# untitled.net
KiCad netlist of a schematic drawn in EAGLE
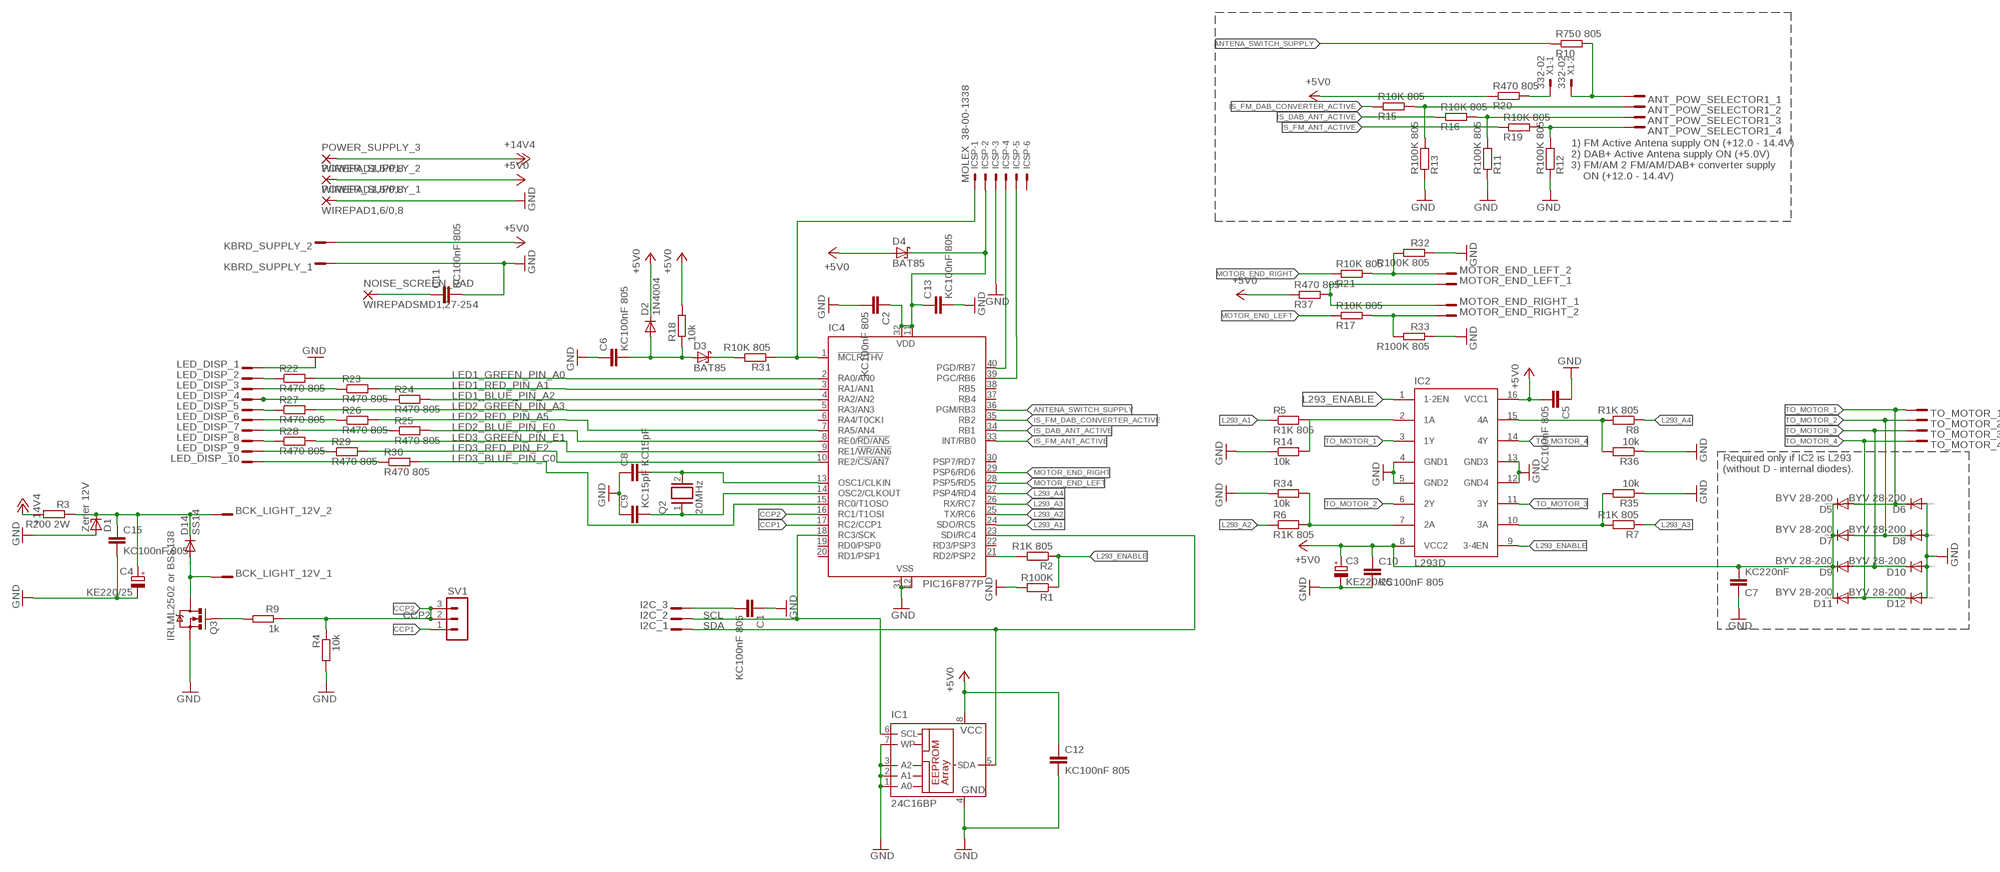
[diagram p0: schematic, sheet 1]

(export (version "E")
  (design (tool "Eeschema 10.0.6"))
  (components
    (comp (ref "ANT_POW_SELECTOR1")
      (value "JST_4_PIN_B4B-PH-KS")
      (footprint "eagle-import:B4B-PH-KS")
      (libsource (lib "eagle-import") (part "JST_4_PIN_B4B-PH-KS"))
    )
    (comp (ref "BCK_LIGHT_12V")
      (value "JST_2_PIN_B2B-XH-A")
      (footprint "eagle-import:B2B-XH-A")
      (libsource (lib "eagle-import") (part "JST_2_PIN_B2B-XH-A"))
    )
    (comp (ref "C1")
      (value "KC100nF 805")
      (footprint "eagle-import:C0805")
      (libsource (lib "eagle-import") (part "C-EUC0805"))
    )
    (comp (ref "C2")
      (value "KC100nF 805")
      (footprint "eagle-import:C0805")
      (libsource (lib "eagle-import") (part "C-EUC0805"))
    )
    (comp (ref "C3")
      (value "KE220/25")
      (footprint "eagle-import:E3,5-8")
      (libsource (lib "eagle-import") (part "CPOL-EUE3.5-8"))
    )
    (comp (ref "C4")
      (value "KE220/25")
      (footprint "eagle-import:TT2D7")
      (libsource (lib "eagle-import") (part "CPOL-EUTT2D7"))
    )
    (comp (ref "C5")
      (value "KC100nF 805")
      (footprint "eagle-import:C0805")
      (libsource (lib "eagle-import") (part "C-EUC0805"))
    )
    (comp (ref "C6")
      (value "KC100nF 805")
      (footprint "eagle-import:C0805")
      (libsource (lib "eagle-import") (part "C-EUC0805"))
    )
    (comp (ref "C7")
      (value "KC220nF")
      (footprint "eagle-import:C050-030X075")
      (libsource (lib "eagle-import") (part "C-EU050-030X075"))
    )
    (comp (ref "C8")
      (value "KC15pF")
      (footprint "eagle-import:C025-030X050")
      (libsource (lib "eagle-import") (part "C-EU025-030X050"))
    )
    (comp (ref "C9")
      (value "KC15pF")
      (footprint "eagle-import:C025-030X050")
      (libsource (lib "eagle-import") (part "C-EU025-030X050"))
    )
    (comp (ref "C10")
      (value "KC100nF 805")
      (footprint "eagle-import:C0805")
      (libsource (lib "eagle-import") (part "C-EUC0805"))
    )
    (comp (ref "C11")
      (value "KC100nF 805")
      (footprint "eagle-import:C0805")
      (libsource (lib "eagle-import") (part "C-EUC0805"))
    )
    (comp (ref "C12")
      (value "KC100nF 805")
      (footprint "eagle-import:C0805")
      (libsource (lib "eagle-import") (part "C-EUC0805"))
    )
    (comp (ref "C13")
      (value "KC100nF 805")
      (footprint "eagle-import:C0805")
      (libsource (lib "eagle-import") (part "C-EUC0805"))
    )
    (comp (ref "C15")
      (value "KC100nF 805")
      (footprint "eagle-import:C0805")
      (libsource (lib "eagle-import") (part "C-EUC0805"))
    )
    (comp (ref "D1")
      (value "Zener 12V")
      (footprint "eagle-import:ZDIO-5")
      (libsource (lib "eagle-import") (part "ZENER-DIODEZD-5"))
    )
    (comp (ref "D2")
      (value "1N4004")
      (footprint "eagle-import:DO41-7.6")
      (libsource (lib "eagle-import") (part "1N4004DO41-7.6"))
    )
    (comp (ref "D3")
      (value "BAT85")
      (footprint "eagle-import:DO34-5")
      (libsource (lib "eagle-import") (part "BAT85DO34-5"))
    )
    (comp (ref "D4")
      (value "BAT85")
      (footprint "eagle-import:DO34-5")
      (libsource (lib "eagle-import") (part "BAT85DO34-5"))
    )
    (comp (ref "D5")
      (value "BYV 28-200")
      (footprint "eagle-import:SOD64-10")
      (libsource (lib "eagle-import") (part "BYV28"))
    )
    (comp (ref "D6")
      (value "BYV 28-200")
      (footprint "eagle-import:SOD64-10")
      (libsource (lib "eagle-import") (part "BYV28"))
    )
    (comp (ref "D7")
      (value "BYV 28-200")
      (footprint "eagle-import:SOD64-10")
      (libsource (lib "eagle-import") (part "BYV28"))
    )
    (comp (ref "D8")
      (value "BYV 28-200")
      (footprint "eagle-import:SOD64-10")
      (libsource (lib "eagle-import") (part "BYV28"))
    )
    (comp (ref "D9")
      (value "BYV 28-200")
      (footprint "eagle-import:SOD64-10")
      (libsource (lib "eagle-import") (part "BYV28"))
    )
    (comp (ref "D10")
      (value "BYV 28-200")
      (footprint "eagle-import:SOD64-10")
      (libsource (lib "eagle-import") (part "BYV28"))
    )
    (comp (ref "D11")
      (value "BYV 28-200")
      (footprint "eagle-import:SOD64-10")
      (libsource (lib "eagle-import") (part "BYV28"))
    )
    (comp (ref "D12")
      (value "BYV 28-200")
      (footprint "eagle-import:SOD64-10")
      (libsource (lib "eagle-import") (part "BYV28"))
    )
    (comp (ref "D14")
      (value "SS14")
      (footprint "eagle-import:SMB")
      (libsource (lib "eagle-import") (part "DIODE-SMB"))
    )
    (comp (ref "I2C")
      (value "JST_3_PIN_B3B-PH-KS")
      (footprint "eagle-import:B3B-PH-KS")
      (libsource (lib "eagle-import") (part "JST_3_PIN_B3B-PH-KS"))
    )
    (comp (ref "IC1")
      (value "24C16BP")
      (footprint "eagle-import:DIL8")
      (fields (field (name "MPN") "AT24C16B-PU"))
      (libsource (lib "eagle-import") (part "24PC16B"))
    )
    (comp (ref "IC2")
      (value "L293D")
      (footprint "eagle-import:DIL16")
      (libsource (lib "eagle-import") (part "L293D"))
    )
    (comp (ref "IC4")
      (value "PIC16F877P")
      (footprint "eagle-import:DIL40")
      (fields (field (name "MF") "MICROCHIP") (field (name "MPN") "PIC16F877-04/P"))
      (libsource (lib "eagle-import") (part "PIC16F87P7"))
    )
    (comp (ref "ICSP")
      (value "MOLEX 38-00-1338")
      (footprint "eagle-import:6410-06")
      (libsource (lib "eagle-import") (part "22-?-0627-2061"))
    )
    (comp (ref "KBRD_SUPPLY")
      (value "JST_2_PIN_B2B-PH-KS")
      (footprint "eagle-import:B2B-PH-KS")
      (libsource (lib "eagle-import") (part "JST_2_PIN_B2B-PH-KS"))
    )
    (comp (ref "LED_DISP")
      (value "JST_10_PIN_B10B-PH-KS")
      (footprint "eagle-import:B10B-PH-KS")
      (libsource (lib "eagle-import") (part "JST_10_PIN_B10B-PH-KS"))
    )
    (comp (ref "MOTOR_END_LEFT")
      (value "JST_2_PIN_B2B-PH-KS")
      (footprint "eagle-import:B2B-PH-KS")
      (libsource (lib "eagle-import") (part "JST_2_PIN_B2B-PH-KS"))
    )
    (comp (ref "MOTOR_END_RIGHT")
      (value "JST_2_PIN_B2B-PH-KS")
      (footprint "eagle-import:B2B-PH-KS")
      (libsource (lib "eagle-import") (part "JST_2_PIN_B2B-PH-KS"))
    )
    (comp (ref "NOISE_SCREEN_PAD")
      (value "WIREPADSMD1,27-254")
      (footprint "eagle-import:SMD1,27-2,54")
      (libsource (lib "eagle-import") (part "WIREPADSMD1,27-254"))
    )
    (comp (ref "POWER_SUPPLY_1")
      (value "WIREPAD1,6/0,8")
      (footprint "eagle-import:1,6_0,8")
      (libsource (lib "eagle-import") (part "WIREPAD1,6/0,8"))
    )
    (comp (ref "POWER_SUPPLY_2")
      (value "WIREPAD1,6/0,8")
      (footprint "eagle-import:1,6_0,8")
      (libsource (lib "eagle-import") (part "WIREPAD1,6/0,8"))
    )
    (comp (ref "POWER_SUPPLY_3")
      (value "WIREPAD1,6/0,8")
      (footprint "eagle-import:1,6_0,8")
      (libsource (lib "eagle-import") (part "WIREPAD1,6/0,8"))
    )
    (comp (ref "Q2")
      (value "20MHz")
      (footprint "eagle-import:QS")
      (libsource (lib "eagle-import") (part "XTAL/S"))
    )
    (comp (ref "Q3")
      (value "IRLML2502 or BSS138")
      (footprint "eagle-import:SOT23-3")
      (libsource (lib "eagle-import") (part "MOSFET-NCHANNELSMD"))
    )
    (comp (ref "R1")
      (value "R100K")
      (footprint "eagle-import:0204_7")
      (libsource (lib "eagle-import") (part "resistor_R-EU_0204/7"))
    )
    (comp (ref "R2")
      (value "R1K 805")
      (footprint "eagle-import:R0805")
      (libsource (lib "eagle-import") (part "resistor_R-EU_R0805"))
    )
    (comp (ref "R3")
      (value "R200 2W")
      (footprint "eagle-import:0207_12")
      (libsource (lib "eagle-import") (part "R-EU_0207/12"))
    )
    (comp (ref "R4")
      (value "10k")
      (footprint "eagle-import:M0805")
      (libsource (lib "eagle-import") (part "R-EU_M0805"))
    )
    (comp (ref "R5")
      (value "R1K 805")
      (footprint "eagle-import:R0805")
      (libsource (lib "eagle-import") (part "resistor_R-EU_R0805"))
    )
    (comp (ref "R6")
      (value "R1K 805")
      (footprint "eagle-import:R0805")
      (libsource (lib "eagle-import") (part "resistor_R-EU_R0805"))
    )
    (comp (ref "R7")
      (value "R1K 805")
      (footprint "eagle-import:R0805")
      (libsource (lib "eagle-import") (part "resistor_R-EU_R0805"))
    )
    (comp (ref "R8")
      (value "R1K 805")
      (footprint "eagle-import:R0805")
      (libsource (lib "eagle-import") (part "resistor_R-EU_R0805"))
    )
    (comp (ref "R9")
      (value "1k")
      (footprint "eagle-import:0207_12")
      (libsource (lib "eagle-import") (part "R-EU_0207/12"))
    )
    (comp (ref "R10")
      (value "R750 805")
      (footprint "eagle-import:R0805")
      (libsource (lib "eagle-import") (part "resistor_R-EU_R0805"))
    )
    (comp (ref "R11")
      (value "R100K 805")
      (footprint "eagle-import:R0805")
      (libsource (lib "eagle-import") (part "resistor_R-EU_R0805"))
    )
    (comp (ref "R12")
      (value "R100K 805")
      (footprint "eagle-import:R0805")
      (libsource (lib "eagle-import") (part "resistor_R-EU_R0805"))
    )
    (comp (ref "R13")
      (value "R100K 805")
      (footprint "eagle-import:R0805")
      (libsource (lib "eagle-import") (part "resistor_R-EU_R0805"))
    )
    (comp (ref "R14")
      (value "10k")
      (footprint "eagle-import:0204V")
      (libsource (lib "eagle-import") (part "resistor_R-EU_0204/2V"))
    )
    (comp (ref "R15")
      (value "R10K 805")
      (footprint "eagle-import:R0805")
      (libsource (lib "eagle-import") (part "resistor_R-EU_R0805"))
    )
    (comp (ref "R16")
      (value "R10K 805")
      (footprint "eagle-import:R0805")
      (libsource (lib "eagle-import") (part "resistor_R-EU_R0805"))
    )
    (comp (ref "R17")
      (value "R10K 805")
      (footprint "eagle-import:R0805")
      (libsource (lib "eagle-import") (part "resistor_R-EU_R0805"))
    )
    (comp (ref "R18")
      (value "10k")
      (footprint "eagle-import:R0805")
      (libsource (lib "eagle-import") (part "resistor_R-EU_R0805"))
    )
    (comp (ref "R19")
      (value "R10K 805")
      (footprint "eagle-import:R0805")
      (libsource (lib "eagle-import") (part "resistor_R-EU_R0805"))
    )
    (comp (ref "R20")
      (value "R470 805")
      (footprint "eagle-import:R0805")
      (libsource (lib "eagle-import") (part "resistor_R-EU_R0805"))
    )
    (comp (ref "R21")
      (value "R10K 805")
      (footprint "eagle-import:R0805")
      (libsource (lib "eagle-import") (part "resistor_R-EU_R0805"))
    )
    (comp (ref "R22")
      (value "R470 805")
      (footprint "eagle-import:R0805")
      (libsource (lib "eagle-import") (part "resistor_R-EU_R0805"))
    )
    (comp (ref "R23")
      (value "R470 805")
      (footprint "eagle-import:R0805")
      (libsource (lib "eagle-import") (part "resistor_R-EU_R0805"))
    )
    (comp (ref "R24")
      (value "R470 805")
      (footprint "eagle-import:R0805")
      (libsource (lib "eagle-import") (part "resistor_R-EU_R0805"))
    )
    (comp (ref "R25")
      (value "R470 805")
      (footprint "eagle-import:R0805")
      (libsource (lib "eagle-import") (part "resistor_R-EU_R0805"))
    )
    (comp (ref "R26")
      (value "R470 805")
      (footprint "eagle-import:R0805")
      (libsource (lib "eagle-import") (part "resistor_R-EU_R0805"))
    )
    (comp (ref "R27")
      (value "R470 805")
      (footprint "eagle-import:R0805")
      (libsource (lib "eagle-import") (part "resistor_R-EU_R0805"))
    )
    (comp (ref "R28")
      (value "R470 805")
      (footprint "eagle-import:R0805")
      (libsource (lib "eagle-import") (part "resistor_R-EU_R0805"))
    )
    (comp (ref "R29")
      (value "R470 805")
      (footprint "eagle-import:R0805")
      (libsource (lib "eagle-import") (part "resistor_R-EU_R0805"))
    )
    (comp (ref "R30")
      (value "R470 805")
      (footprint "eagle-import:R0805")
      (libsource (lib "eagle-import") (part "resistor_R-EU_R0805"))
    )
    (comp (ref "R31")
      (value "R10K 805")
      (footprint "eagle-import:R0805")
      (libsource (lib "eagle-import") (part "resistor_R-EU_R0805"))
    )
    (comp (ref "R32")
      (value "R100K 805")
      (footprint "eagle-import:R0805")
      (libsource (lib "eagle-import") (part "resistor_R-EU_R0805"))
    )
    (comp (ref "R33")
      (value "R100K 805")
      (footprint "eagle-import:R0805")
      (libsource (lib "eagle-import") (part "resistor_R-EU_R0805"))
    )
    (comp (ref "R34")
      (value "10k")
      (footprint "eagle-import:0204_5")
      (libsource (lib "eagle-import") (part "resistor_R-EU_0204/5"))
    )
    (comp (ref "R35")
      (value "10k")
      (footprint "eagle-import:0204_7")
      (libsource (lib "eagle-import") (part "resistor_R-EU_0204/7"))
    )
    (comp (ref "R36")
      (value "10k")
      (footprint "eagle-import:0204_7")
      (libsource (lib "eagle-import") (part "resistor_R-EU_0204/7"))
    )
    (comp (ref "R37")
      (value "R470 805")
      (footprint "eagle-import:R0805")
      (libsource (lib "eagle-import") (part "resistor_R-EU_R0805"))
    )
    (comp (ref "SV1")
      (value "MA03-1")
      (footprint "eagle-import:MA03-1")
      (libsource (lib "eagle-import") (part "MA03-1"))
    )
    (comp (ref "TO_MOTOR")
      (value "JST_4_PIN_B4B-XH-A")
      (footprint "eagle-import:B4B-XH-A")
      (libsource (lib "eagle-import") (part "JST_4_PIN_B4B-XH-A"))
    )
    (comp (ref "X1")
      (value "332-02")
      (footprint "eagle-import:332-02")
      (libsource (lib "eagle-import") (part "332-02"))
    )
  )
  (nets
    (net (code "1") (name "+5V0") (class "Default")
      (node (ref "C10") (pin "1") (pinfunction "1_1") (pintype "passive"))
      (node (ref "C12") (pin "1") (pinfunction "1_1") (pintype "passive"))
      (node (ref "C3") (pin "+") (pinfunction "+_+") (pintype "passive"))
      (node (ref "C5") (pin "2") (pinfunction "2_2") (pintype "passive"))
      (node (ref "C7") (pin "2") (pinfunction "2_2") (pintype "passive"))
      (node (ref "D11") (pin "C") (pinfunction "C_C") (pintype "passive"))
      (node (ref "D2") (pin "C") (pinfunction "C_C") (pintype "passive"))
      (node (ref "D4") (pin "A") (pinfunction "A_A") (pintype "passive"))
      (node (ref "D5") (pin "C") (pinfunction "C_C") (pintype "passive"))
      (node (ref "D7") (pin "C") (pinfunction "C_C") (pintype "passive"))
      (node (ref "D9") (pin "C") (pinfunction "C_C") (pintype "passive"))
      (node (ref "IC1") (pin "8") (pinfunction "VCC_8") (pintype "power_in"))
      (node (ref "IC2") (pin "16") (pinfunction "VCC1_16") (pintype "power_in"))
      (node (ref "IC2") (pin "8") (pinfunction "VCC2_8") (pintype "power_in"))
      (node (ref "KBRD_SUPPLY") (pin "P$2") (pinfunction "P$1_P$2") (pintype "bidirectional"))
      (node (ref "POWER_SUPPLY_2") (pin "1") (pinfunction "P_1") (pintype "passive"))
      (node (ref "R18") (pin "2") (pinfunction "2_2") (pintype "passive"))
      (node (ref "R20") (pin "1") (pinfunction "1_1") (pintype "passive"))
      (node (ref "R37") (pin "1") (pinfunction "1_1") (pintype "passive"))
    )
    (net (code "2") (name "+14V4") (class "Default")
      (node (ref "POWER_SUPPLY_3") (pin "1") (pinfunction "P_1") (pintype "passive"))
      (node (ref "R3") (pin "2") (pinfunction "2_2") (pintype "passive"))
    )
    (net (code "3") (name "/LED1_BLUE_PIN_A2") (class "Default")
      (node (ref "IC4") (pin "4") (pinfunction "RA2/AN2_4") (pintype "bidirectional"))
      (node (ref "R24") (pin "2") (pinfunction "2_2") (pintype "passive"))
    )
    (net (code "4") (name "/LED1_GREEN_PIN_A0") (class "Default")
      (node (ref "IC4") (pin "2") (pinfunction "RA0/AN0_2") (pintype "bidirectional"))
      (node (ref "R22") (pin "2") (pinfunction "2_2") (pintype "passive"))
    )
    (net (code "5") (name "/LED1_RED_PIN_A1") (class "Default")
      (node (ref "IC4") (pin "3") (pinfunction "RA1/AN1_3") (pintype "bidirectional"))
      (node (ref "R23") (pin "2") (pinfunction "2_2") (pintype "passive"))
    )
    (net (code "6") (name "/LED2_BLUE_PIN_E0") (class "Default")
      (node (ref "IC4") (pin "8") (pinfunction "RE0/~{RD/AN5}_8") (pintype "bidirectional"))
      (node (ref "R25") (pin "2") (pinfunction "2_2") (pintype "passive"))
    )
    (net (code "7") (name "/LED2_GREEN_PIN_A3") (class "Default")
      (node (ref "IC4") (pin "5") (pinfunction "RA3/AN3_5") (pintype "bidirectional"))
      (node (ref "R27") (pin "2") (pinfunction "2_2") (pintype "passive"))
    )
    (net (code "8") (name "/LED2_RED_PIN_A5") (class "Default")
      (node (ref "IC4") (pin "7") (pinfunction "RA5/AN4_7") (pintype "bidirectional"))
      (node (ref "R26") (pin "2") (pinfunction "2_2") (pintype "passive"))
    )
    (net (code "9") (name "/LED3_BLUE_PIN_C0") (class "Default")
      (node (ref "IC4") (pin "15") (pinfunction "RC0/T1OSO_15") (pintype "bidirectional"))
      (node (ref "R30") (pin "2") (pinfunction "2_2") (pintype "passive"))
    )
    (net (code "10") (name "/LED3_GREEN_PIN_E1") (class "Default")
      (node (ref "IC4") (pin "9") (pinfunction "RE1/~{WR/AN6}_9") (pintype "bidirectional"))
      (node (ref "R28") (pin "2") (pinfunction "2_2") (pintype "passive"))
    )
    (net (code "11") (name "/LED3_RED_PIN_E2") (class "Default")
      (node (ref "IC4") (pin "10") (pinfunction "RE2/~{CS/AN7}_10") (pintype "bidirectional"))
      (node (ref "R29") (pin "2") (pinfunction "2_2") (pintype "passive"))
    )
    (net (code "12") (name "/SCL") (class "Default")
      (node (ref "I2C") (pin "P$2") (pinfunction "P$1_P$2") (pintype "bidirectional"))
      (node (ref "IC1") (pin "6") (pinfunction "SCL_6") (pintype "input"))
      (node (ref "IC4") (pin "18") (pinfunction "RC3/SCK_18") (pintype "bidirectional"))
    )
    (net (code "13") (name "/SDA") (class "Default")
      (node (ref "I2C") (pin "P$1") (pinfunction "P$1_P$1") (pintype "bidirectional"))
      (node (ref "IC1") (pin "5") (pinfunction "SDA_5") (pintype "bidirectional"))
      (node (ref "IC4") (pin "23") (pinfunction "SDI/RC4_23") (pintype "bidirectional"))
    )
    (net (code "14") (name "ANTENA_SWITCH_SUPPLY") (class "Default")
      (node (ref "IC4") (pin "36") (pinfunction "PGM/RB3_36") (pintype "bidirectional"))
      (node (ref "R10") (pin "1") (pinfunction "1_1") (pintype "passive"))
    )
    (net (code "15") (name "CCP1") (class "Default")
      (node (ref "IC4") (pin "17") (pinfunction "RC2/CCP1_17") (pintype "bidirectional"))
      (node (ref "SV1") (pin "1") (pinfunction "1_1") (pintype "passive"))
    )
    (net (code "16") (name "CCP2") (class "Default")
      (node (ref "IC4") (pin "16") (pinfunction "RC1/T1OSI_16") (pintype "bidirectional"))
      (node (ref "R4") (pin "1") (pinfunction "1_1") (pintype "passive"))
      (node (ref "R9") (pin "1") (pinfunction "1_1") (pintype "passive"))
      (node (ref "SV1") (pin "2") (pinfunction "2_2") (pintype "passive"))
      (node (ref "SV1") (pin "3") (pinfunction "3_3") (pintype "passive"))
    )
    (net (code "17") (name "GND") (class "Default")
      (node (ref "C1") (pin "1") (pinfunction "1_1") (pintype "passive"))
      (node (ref "C10") (pin "2") (pinfunction "2_2") (pintype "passive"))
      (node (ref "C11") (pin "2") (pinfunction "2_2") (pintype "passive"))
      (node (ref "C12") (pin "2") (pinfunction "2_2") (pintype "passive"))
      (node (ref "C13") (pin "2") (pinfunction "2_2") (pintype "passive"))
      (node (ref "C15") (pin "2") (pinfunction "2_2") (pintype "passive"))
      (node (ref "C2") (pin "2") (pinfunction "2_2") (pintype "passive"))
      (node (ref "C3") (pin "-") (pinfunction "-_-") (pintype "passive"))
      (node (ref "C4") (pin "-") (pinfunction "-_-") (pintype "passive"))
      (node (ref "C5") (pin "1") (pinfunction "1_1") (pintype "passive"))
      (node (ref "C6") (pin "1") (pinfunction "1_1") (pintype "passive"))
      (node (ref "C7") (pin "1") (pinfunction "1_1") (pintype "passive"))
      (node (ref "C8") (pin "1") (pinfunction "1_1") (pintype "passive"))
      (node (ref "C9") (pin "1") (pinfunction "1_1") (pintype "passive"))
      (node (ref "D1") (pin "A") (pinfunction "A_A") (pintype "passive"))
      (node (ref "D10") (pin "A") (pinfunction "A_A") (pintype "passive"))
      (node (ref "D12") (pin "A") (pinfunction "A_A") (pintype "passive"))
      (node (ref "D6") (pin "A") (pinfunction "A_A") (pintype "passive"))
      (node (ref "D8") (pin "A") (pinfunction "A_A") (pintype "passive"))
      (node (ref "IC1") (pin "1") (pinfunction "A0_1") (pintype "input"))
      (node (ref "IC1") (pin "2") (pinfunction "A1_2") (pintype "input"))
      (node (ref "IC1") (pin "3") (pinfunction "A2_3") (pintype "input"))
      (node (ref "IC1") (pin "4") (pinfunction "GND_4") (pintype "power_in"))
      (node (ref "IC1") (pin "7") (pinfunction "WP_7") (pintype "input"))
      (node (ref "IC2") (pin "12") (pinfunction "GND4_12") (pintype "power_in"))
      (node (ref "IC2") (pin "13") (pinfunction "GND3_13") (pintype "power_in"))
      (node (ref "IC2") (pin "4") (pinfunction "GND1_4") (pintype "power_in"))
      (node (ref "IC2") (pin "5") (pinfunction "GND2_5") (pintype "power_in"))
      (node (ref "IC4") (pin "12") (pinfunction "VSS_12") (pintype "power_in"))
      (node (ref "IC4") (pin "31") (pinfunction "VSS_31") (pintype "power_in"))
      (node (ref "ICSP") (pin "3") (pinfunction "S_3") (pintype "passive"))
      (node (ref "KBRD_SUPPLY") (pin "P$1") (pinfunction "P$1_P$1") (pintype "bidirectional"))
      (node (ref "LED_DISP") (pin "P$1") (pinfunction "P$1_P$1") (pintype "bidirectional"))
      (node (ref "POWER_SUPPLY_1") (pin "1") (pinfunction "P_1") (pintype "passive"))
      (node (ref "Q3") (pin "2") (pinfunction "S_2") (pintype "passive"))
      (node (ref "R1") (pin "2") (pinfunction "2_2") (pintype "passive"))
      (node (ref "R11") (pin "1") (pinfunction "1_1") (pintype "passive"))
      (node (ref "R12") (pin "1") (pinfunction "1_1") (pintype "passive"))
      (node (ref "R13") (pin "1") (pinfunction "1_1") (pintype "passive"))
      (node (ref "R14") (pin "1") (pinfunction "1_1") (pintype "passive"))
      (node (ref "R32") (pin "1") (pinfunction "1_1") (pintype "passive"))
      (node (ref "R33") (pin "1") (pinfunction "1_1") (pintype "passive"))
      (node (ref "R34") (pin "1") (pinfunction "1_1") (pintype "passive"))
      (node (ref "R35") (pin "1") (pinfunction "1_1") (pintype "passive"))
      (node (ref "R36") (pin "1") (pinfunction "1_1") (pintype "passive"))
      (node (ref "R4") (pin "2") (pinfunction "2_2") (pintype "passive"))
    )
    (net (code "18") (name "IS_DAB_ANT_ACTIVE") (class "Default")
      (node (ref "IC4") (pin "34") (pinfunction "RB1_34") (pintype "bidirectional"))
      (node (ref "R16") (pin "1") (pinfunction "1_1") (pintype "passive"))
    )
    (net (code "19") (name "IS_FM_ANT_ACTIVE") (class "Default")
      (node (ref "IC4") (pin "33") (pinfunction "INT/RB0_33") (pintype "bidirectional"))
      (node (ref "R19") (pin "1") (pinfunction "1_1") (pintype "passive"))
    )
    (net (code "20") (name "IS_FM_DAB_CONVERTER_ACTIVE") (class "Default")
      (node (ref "IC4") (pin "35") (pinfunction "RB2_35") (pintype "bidirectional"))
      (node (ref "R15") (pin "1") (pinfunction "1_1") (pintype "passive"))
    )
    (net (code "21") (name "L293_A1") (class "Default")
      (node (ref "IC4") (pin "24") (pinfunction "SDO/RC5_24") (pintype "bidirectional"))
      (node (ref "R5") (pin "1") (pinfunction "1_1") (pintype "passive"))
    )
    (net (code "22") (name "L293_A2") (class "Default")
      (node (ref "IC4") (pin "25") (pinfunction "TX/RC6_25") (pintype "bidirectional"))
      (node (ref "R6") (pin "1") (pinfunction "1_1") (pintype "passive"))
    )
    (net (code "23") (name "L293_A3") (class "Default")
      (node (ref "IC4") (pin "26") (pinfunction "RX/RC7_26") (pintype "bidirectional"))
      (node (ref "R7") (pin "1") (pinfunction "1_1") (pintype "passive"))
    )
    (net (code "24") (name "L293_A4") (class "Default")
      (node (ref "IC4") (pin "27") (pinfunction "PSP4/RD4_27") (pintype "bidirectional"))
      (node (ref "R8") (pin "1") (pinfunction "1_1") (pintype "passive"))
    )
    (net (code "25") (name "L293_ENABLE") (class "Default")
      (node (ref "IC2") (pin "1") (pinfunction "1-2EN_1") (pintype "input"))
      (node (ref "IC2") (pin "9") (pinfunction "3-4EN_9") (pintype "input"))
      (node (ref "R1") (pin "1") (pinfunction "1_1") (pintype "passive"))
      (node (ref "R2") (pin "1") (pinfunction "1_1") (pintype "passive"))
    )
    (net (code "26") (name "MOTOR_END_LEFT") (class "Default")
      (node (ref "IC4") (pin "28") (pinfunction "PSP5/RD5_28") (pintype "bidirectional"))
      (node (ref "R17") (pin "1") (pinfunction "1_1") (pintype "passive"))
    )
    (net (code "27") (name "MOTOR_END_RIGHT") (class "Default")
      (node (ref "IC4") (pin "29") (pinfunction "PSP6/RD6_29") (pintype "bidirectional"))
      (node (ref "R21") (pin "1") (pinfunction "1_1") (pintype "passive"))
    )
    (net (code "28") (name "Net-(ANT_POW_SELECTOR1B-P$1)") (class "Default")
      (node (ref "ANT_POW_SELECTOR1") (pin "P$2") (pinfunction "P$1_P$2") (pintype "bidirectional"))
      (node (ref "R13") (pin "2") (pinfunction "2_2") (pintype "passive"))
      (node (ref "R15") (pin "2") (pinfunction "2_2") (pintype "passive"))
    )
    (net (code "29") (name "Net-(ANT_POW_SELECTOR1C-P$1)") (class "Default")
      (node (ref "ANT_POW_SELECTOR1") (pin "P$3") (pinfunction "P$1_P$3") (pintype "bidirectional"))
      (node (ref "R11") (pin "2") (pinfunction "2_2") (pintype "passive"))
      (node (ref "R16") (pin "2") (pinfunction "2_2") (pintype "passive"))
    )
    (net (code "30") (name "Net-(ANT_POW_SELECTOR1D-P$1)") (class "Default")
      (node (ref "ANT_POW_SELECTOR1") (pin "P$4") (pinfunction "P$1_P$4") (pintype "bidirectional"))
      (node (ref "R12") (pin "2") (pinfunction "2_2") (pintype "passive"))
      (node (ref "R19") (pin "2") (pinfunction "2_2") (pintype "passive"))
    )
    (net (code "31") (name "Net-(BCK_LIGHT_12VB-P$1)") (class "Default")
      (node (ref "BCK_LIGHT_12V") (pin "P$2") (pinfunction "P$1_P$2") (pintype "bidirectional"))
      (node (ref "C15") (pin "1") (pinfunction "1_1") (pintype "passive"))
      (node (ref "C4") (pin "+") (pinfunction "+_+") (pintype "passive"))
      (node (ref "D1") (pin "C") (pinfunction "C_C") (pintype "passive"))
      (node (ref "D14") (pin "C") (pinfunction "C_C") (pintype "passive"))
      (node (ref "R3") (pin "1") (pinfunction "1_1") (pintype "passive"))
    )
    (net (code "32") (name "Net-(C6-Pad2)") (class "Default")
      (node (ref "C6") (pin "2") (pinfunction "2_2") (pintype "passive"))
      (node (ref "D2") (pin "A") (pinfunction "A_A") (pintype "passive"))
      (node (ref "D3") (pin "A") (pinfunction "A_A") (pintype "passive"))
      (node (ref "R18") (pin "1") (pinfunction "1_1") (pintype "passive"))
    )
    (net (code "33") (name "Net-(D3-PadC)") (class "Default")
      (node (ref "D3") (pin "C") (pinfunction "C_C") (pintype "passive"))
      (node (ref "R31") (pin "2") (pinfunction "2_2") (pintype "passive"))
    )
    (net (code "34") (name "Net-(I2CC-P$1)") (class "Default")
      (node (ref "C1") (pin "2") (pinfunction "2_2") (pintype "passive"))
      (node (ref "I2C") (pin "P$3") (pinfunction "P$1_P$3") (pintype "bidirectional"))
    )
    (net (code "35") (name "Net-(IC2-1A)") (class "Default")
      (node (ref "IC2") (pin "2") (pinfunction "1A_2") (pintype "input"))
      (node (ref "R14") (pin "2") (pinfunction "2_2") (pintype "passive"))
      (node (ref "R5") (pin "2") (pinfunction "2_2") (pintype "passive"))
    )
    (net (code "36") (name "Net-(IC2-2A)") (class "Default")
      (node (ref "IC2") (pin "7") (pinfunction "2A_7") (pintype "input"))
      (node (ref "R34") (pin "2") (pinfunction "2_2") (pintype "passive"))
      (node (ref "R6") (pin "2") (pinfunction "2_2") (pintype "passive"))
    )
    (net (code "37") (name "Net-(IC2-3A)") (class "Default")
      (node (ref "IC2") (pin "10") (pinfunction "3A_10") (pintype "input"))
      (node (ref "R35") (pin "2") (pinfunction "2_2") (pintype "passive"))
      (node (ref "R7") (pin "2") (pinfunction "2_2") (pintype "passive"))
    )
    (net (code "38") (name "Net-(IC2-4A)") (class "Default")
      (node (ref "IC2") (pin "15") (pinfunction "4A_15") (pintype "input"))
      (node (ref "R36") (pin "2") (pinfunction "2_2") (pintype "passive"))
      (node (ref "R8") (pin "2") (pinfunction "2_2") (pintype "passive"))
    )
    (net (code "39") (name "Net-(IC4-OSC1{slash}CLKIN)") (class "Default")
      (node (ref "C8") (pin "2") (pinfunction "2_2") (pintype "passive"))
      (node (ref "IC4") (pin "13") (pinfunction "OSC1/CLKIN_13") (pintype "input"))
      (node (ref "Q2") (pin "2") (pinfunction "2_2") (pintype "passive"))
    )
    (net (code "40") (name "Net-(IC4-OSC2{slash}CLKOUT)") (class "Default")
      (node (ref "C9") (pin "2") (pinfunction "2_2") (pintype "passive"))
      (node (ref "IC4") (pin "14") (pinfunction "OSC2/CLKOUT_14") (pintype "output"))
      (node (ref "Q2") (pin "1") (pinfunction "1_1") (pintype "passive"))
    )
    (net (code "41") (name "Net-(IC4-PGC{slash}RB6)") (class "Default")
      (node (ref "IC4") (pin "39") (pinfunction "PGC/RB6_39") (pintype "bidirectional"))
      (node (ref "ICSP") (pin "5") (pinfunction "S_5") (pintype "passive"))
    )
    (net (code "42") (name "Net-(IC4-PGD{slash}RB7)") (class "Default")
      (node (ref "IC4") (pin "40") (pinfunction "PGD/RB7_40") (pintype "bidirectional"))
      (node (ref "ICSP") (pin "4") (pinfunction "S_4") (pintype "passive"))
    )
    (net (code "43") (name "Net-(IC4-RD2{slash}PSP2)") (class "Default")
      (node (ref "IC4") (pin "21") (pinfunction "RD2/PSP2_21") (pintype "bidirectional"))
      (node (ref "R2") (pin "2") (pinfunction "2_2") (pintype "passive"))
    )
    (net (code "44") (name "Net-(IC4-~{MCLR{slash}THV})") (class "Default")
      (node (ref "IC4") (pin "1") (pinfunction "~{MCLR/THV}_1") (pintype "input"))
      (node (ref "ICSP") (pin "1") (pinfunction "S_1") (pintype "passive"))
      (node (ref "R31") (pin "1") (pinfunction "1_1") (pintype "passive"))
    )
    (net (code "45") (name "Net-(ICSPB-S)") (class "Default")
      (node (ref "C13") (pin "1") (pinfunction "1_1") (pintype "passive"))
      (node (ref "C2") (pin "1") (pinfunction "1_1") (pintype "passive"))
      (node (ref "D4") (pin "C") (pinfunction "C_C") (pintype "passive"))
      (node (ref "IC4") (pin "11") (pinfunction "VDD_11") (pintype "power_in"))
      (node (ref "IC4") (pin "32") (pinfunction "VDD_32") (pintype "power_in"))
      (node (ref "ICSP") (pin "2") (pinfunction "S_2") (pintype "passive"))
    )
    (net (code "46") (name "Net-(LED_DISPB-P$1)") (class "Default")
      (node (ref "LED_DISP") (pin "P$10") (pinfunction "P$1_P$10") (pintype "bidirectional"))
      (node (ref "R30") (pin "1") (pinfunction "1_1") (pintype "passive"))
    )
    (net (code "47") (name "Net-(LED_DISPC-P$1)") (class "Default")
      (node (ref "LED_DISP") (pin "P$2") (pinfunction "P$1_P$2") (pintype "bidirectional"))
      (node (ref "R22") (pin "1") (pinfunction "1_1") (pintype "passive"))
    )
    (net (code "48") (name "Net-(LED_DISPD-P$1)") (class "Default")
      (node (ref "LED_DISP") (pin "P$3") (pinfunction "P$1_P$3") (pintype "bidirectional"))
      (node (ref "R23") (pin "1") (pinfunction "1_1") (pintype "passive"))
    )
    (net (code "49") (name "Net-(LED_DISPE-P$1)") (class "Default")
      (node (ref "LED_DISP") (pin "P$4") (pinfunction "P$1_P$4") (pintype "bidirectional"))
      (node (ref "R24") (pin "1") (pinfunction "1_1") (pintype "passive"))
    )
    (net (code "50") (name "Net-(LED_DISPF-P$1)") (class "Default")
      (node (ref "LED_DISP") (pin "P$5") (pinfunction "P$1_P$5") (pintype "bidirectional"))
      (node (ref "R27") (pin "1") (pinfunction "1_1") (pintype "passive"))
    )
    (net (code "51") (name "Net-(LED_DISPG-P$1)") (class "Default")
      (node (ref "LED_DISP") (pin "P$6") (pinfunction "P$1_P$6") (pintype "bidirectional"))
      (node (ref "R26") (pin "1") (pinfunction "1_1") (pintype "passive"))
    )
    (net (code "52") (name "Net-(LED_DISPH-P$1)") (class "Default")
      (node (ref "LED_DISP") (pin "P$7") (pinfunction "P$1_P$7") (pintype "bidirectional"))
      (node (ref "R25") (pin "1") (pinfunction "1_1") (pintype "passive"))
    )
    (net (code "53") (name "Net-(LED_DISPI-P$1)") (class "Default")
      (node (ref "LED_DISP") (pin "P$8") (pinfunction "P$1_P$8") (pintype "bidirectional"))
      (node (ref "R28") (pin "1") (pinfunction "1_1") (pintype "passive"))
    )
    (net (code "54") (name "Net-(LED_DISPJ-P$1)") (class "Default")
      (node (ref "LED_DISP") (pin "P$9") (pinfunction "P$1_P$9") (pintype "bidirectional"))
      (node (ref "R29") (pin "1") (pinfunction "1_1") (pintype "passive"))
    )
    (net (code "55") (name "Net-(MOTOR_END_LEFT-PadP$1)") (class "Default")
      (node (ref "MOTOR_END_LEFT") (pin "P$1") (pinfunction "P$1_P$1") (pintype "bidirectional"))
      (node (ref "MOTOR_END_RIGHT") (pin "P$1") (pinfunction "P$1_P$1") (pintype "bidirectional"))
      (node (ref "R37") (pin "2") (pinfunction "2_2") (pintype "passive"))
    )
    (net (code "56") (name "Net-(MOTOR_END_LEFTB-P$1)") (class "Default")
      (node (ref "MOTOR_END_LEFT") (pin "P$2") (pinfunction "P$1_P$2") (pintype "bidirectional"))
      (node (ref "R21") (pin "2") (pinfunction "2_2") (pintype "passive"))
      (node (ref "R32") (pin "2") (pinfunction "2_2") (pintype "passive"))
    )
    (net (code "57") (name "Net-(MOTOR_END_RIGHTB-P$1)") (class "Default")
      (node (ref "MOTOR_END_RIGHT") (pin "P$2") (pinfunction "P$1_P$2") (pintype "bidirectional"))
      (node (ref "R17") (pin "2") (pinfunction "2_2") (pintype "passive"))
      (node (ref "R33") (pin "2") (pinfunction "2_2") (pintype "passive"))
    )
    (net (code "58") (name "Net-(NOISE_SCREEN_PAD-P)") (class "Default")
      (node (ref "C11") (pin "1") (pinfunction "1_1") (pintype "passive"))
      (node (ref "NOISE_SCREEN_PAD") (pin "1") (pinfunction "P_1") (pintype "passive"))
    )
    (net (code "59") (name "Net-(Q3-D)") (class "Default")
      (node (ref "BCK_LIGHT_12V") (pin "P$1") (pinfunction "P$1_P$1") (pintype "bidirectional"))
      (node (ref "D14") (pin "A") (pinfunction "A_A") (pintype "passive"))
      (node (ref "Q3") (pin "3") (pinfunction "D_3") (pintype "passive"))
    )
    (net (code "60") (name "Net-(Q3-G)") (class "Default")
      (node (ref "Q3") (pin "1") (pinfunction "G_1") (pintype "passive"))
      (node (ref "R9") (pin "2") (pinfunction "2_2") (pintype "passive"))
    )
    (net (code "61") (name "Net-(X1A-S)") (class "Default")
      (node (ref "R20") (pin "2") (pinfunction "2_2") (pintype "passive"))
      (node (ref "X1") (pin "1") (pinfunction "S_1") (pintype "passive"))
    )
    (net (code "62") (name "Net-(X1B-S)") (class "Default")
      (node (ref "ANT_POW_SELECTOR1") (pin "P$1") (pinfunction "P$1_P$1") (pintype "bidirectional"))
      (node (ref "R10") (pin "2") (pinfunction "2_2") (pintype "passive"))
      (node (ref "X1") (pin "2") (pinfunction "S_2") (pintype "passive"))
    )
    (net (code "63") (name "TO_MOTOR_1") (class "Default")
      (node (ref "D5") (pin "A") (pinfunction "A_A") (pintype "passive"))
      (node (ref "D6") (pin "C") (pinfunction "C_C") (pintype "passive"))
      (node (ref "IC2") (pin "3") (pinfunction "1Y_3") (pintype "output"))
      (node (ref "TO_MOTOR") (pin "P$1") (pinfunction "P$1_P$1") (pintype "bidirectional"))
    )
    (net (code "64") (name "TO_MOTOR_2") (class "Default")
      (node (ref "D7") (pin "A") (pinfunction "A_A") (pintype "passive"))
      (node (ref "D8") (pin "C") (pinfunction "C_C") (pintype "passive"))
      (node (ref "IC2") (pin "6") (pinfunction "2Y_6") (pintype "output"))
      (node (ref "TO_MOTOR") (pin "P$2") (pinfunction "P$1_P$2") (pintype "bidirectional"))
    )
    (net (code "65") (name "TO_MOTOR_3") (class "Default")
      (node (ref "D10") (pin "C") (pinfunction "C_C") (pintype "passive"))
      (node (ref "D9") (pin "A") (pinfunction "A_A") (pintype "passive"))
      (node (ref "IC2") (pin "11") (pinfunction "3Y_11") (pintype "output"))
      (node (ref "TO_MOTOR") (pin "P$3") (pinfunction "P$1_P$3") (pintype "bidirectional"))
    )
    (net (code "66") (name "TO_MOTOR_4") (class "Default")
      (node (ref "D11") (pin "A") (pinfunction "A_A") (pintype "passive"))
      (node (ref "D12") (pin "C") (pinfunction "C_C") (pintype "passive"))
      (node (ref "IC2") (pin "14") (pinfunction "4Y_14") (pintype "output"))
      (node (ref "TO_MOTOR") (pin "P$4") (pinfunction "P$1_P$4") (pintype "bidirectional"))
    )
    (net (code "67") (name "unconnected-(IC4-PSP7{slash}RD7-Pad30)") (class "Default")
      (node (ref "IC4") (pin "30") (pinfunction "PSP7/RD7_30") (pintype "bidirectional"))
    )
    (net (code "68") (name "unconnected-(IC4-RA4{slash}T0CKI-Pad6)") (class "Default")
      (node (ref "IC4") (pin "6") (pinfunction "RA4/T0CKI_6") (pintype "bidirectional"))
    )
    (net (code "69") (name "unconnected-(IC4-RB4-Pad37)") (class "Default")
      (node (ref "IC4") (pin "37") (pinfunction "RB4_37") (pintype "bidirectional"))
    )
    (net (code "70") (name "unconnected-(IC4-RB5-Pad38)") (class "Default")
      (node (ref "IC4") (pin "38") (pinfunction "RB5_38") (pintype "bidirectional"))
    )
    (net (code "71") (name "unconnected-(IC4-RD0{slash}PSP0-Pad19)") (class "Default")
      (node (ref "IC4") (pin "19") (pinfunction "RD0/PSP0_19") (pintype "bidirectional"))
    )
    (net (code "72") (name "unconnected-(IC4-RD1{slash}PSP1-Pad20)") (class "Default")
      (node (ref "IC4") (pin "20") (pinfunction "RD1/PSP1_20") (pintype "bidirectional"))
    )
    (net (code "73") (name "unconnected-(IC4-RD3{slash}PSP3-Pad22)") (class "Default")
      (node (ref "IC4") (pin "22") (pinfunction "RD3/PSP3_22") (pintype "bidirectional"))
    )
    (net (code "74") (name "unconnected-(ICSPF-S-Pad6)") (class "Default")
      (node (ref "ICSP") (pin "6") (pinfunction "S_6") (pintype "passive"))
    )
  )
)
